# TowerPro_25A_HH30A_V1_1.net
KiCad netlist of a schematic drawn in EAGLE
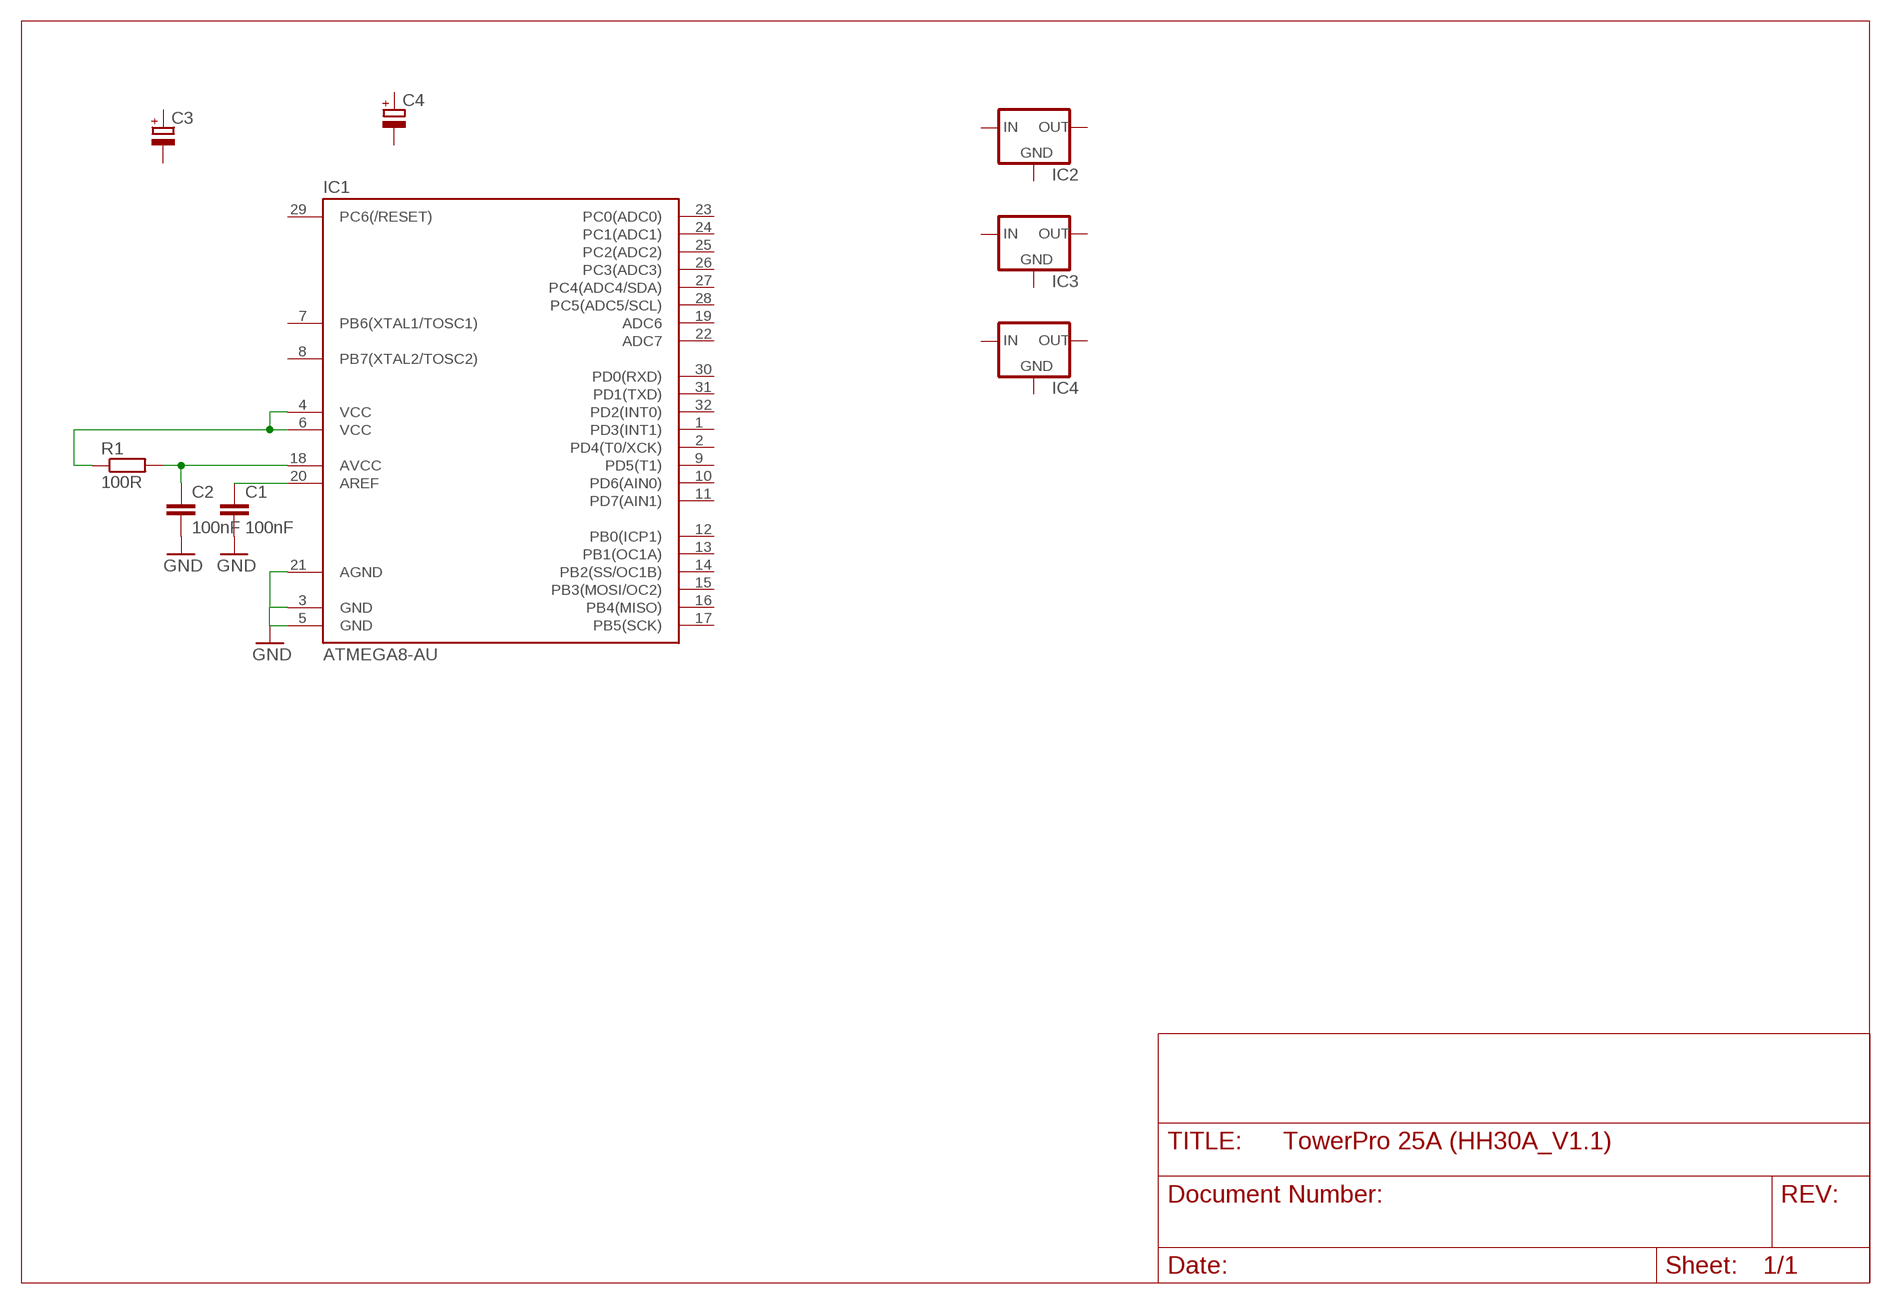
[diagram p0: schematic, sheet 1]

(export (version "E")
  (design (tool "Eeschema 10.0.6"))
  (components
    (comp (ref "C1")
      (value "100nF")
      (footprint "eagle-import:C2.5-3")
      (libsource (lib "eagle-import") (part "C2,5-3"))
    )
    (comp (ref "C2")
      (value "100nF")
      (footprint "eagle-import:C2.5-3")
      (libsource (lib "eagle-import") (part "C2,5-3"))
    )
    (comp (ref "C3")
      (value "CPOL-EUE3.5-10")
      (footprint "eagle-import:E3,5-10")
      (libsource (lib "eagle-import") (part "CPOL-EUE3.5-10"))
    )
    (comp (ref "C4")
      (value "CPOL-EUE3.5-10")
      (footprint "eagle-import:E3,5-10")
      (libsource (lib "eagle-import") (part "CPOL-EUE3.5-10"))
    )
    (comp (ref "IC1")
      (value "ATMEGA8-AU")
      (footprint "eagle-import:TQFP32-08")
      (libsource (lib "eagle-import") (part "ATMEGA8-AU"))
    )
    (comp (ref "IC2")
      (value "78MXXL")
      (footprint "eagle-import:78MXXL")
      (libsource (lib "eagle-import") (part "78MXXL"))
    )
    (comp (ref "IC3")
      (value "78MXXL")
      (footprint "eagle-import:78MXXL")
      (libsource (lib "eagle-import") (part "78MXXL"))
    )
    (comp (ref "IC4")
      (value "78MXXL")
      (footprint "eagle-import:78MXXL")
      (libsource (lib "eagle-import") (part "78MXXL"))
    )
    (comp (ref "R1")
      (value "100R")
      (footprint "eagle-import:M1206")
      (libsource (lib "eagle-import") (part "R-EU_M1206"))
    )
  )
  (nets
    (net (code "1") (name "GND") (class "Default")
      (node (ref "C1") (pin "2") (pinfunction "2_2") (pintype "passive"))
      (node (ref "C2") (pin "2") (pinfunction "2_2") (pintype "passive"))
      (node (ref "IC1") (pin "21") (pinfunction "AGND_21") (pintype "power_in"))
      (node (ref "IC1") (pin "3") (pinfunction "GND_3") (pintype "power_in"))
      (node (ref "IC1") (pin "5") (pinfunction "GND_5") (pintype "power_in"))
    )
    (net (code "2") (name "Net-(IC1-AREF)") (class "Default")
      (node (ref "C1") (pin "1") (pinfunction "1_1") (pintype "passive"))
      (node (ref "IC1") (pin "20") (pinfunction "AREF_20") (pintype "passive"))
    )
    (net (code "3") (name "Net-(IC1-AVCC)") (class "Default")
      (node (ref "C2") (pin "1") (pinfunction "1_1") (pintype "passive"))
      (node (ref "IC1") (pin "18") (pinfunction "AVCC_18") (pintype "passive"))
      (node (ref "R1") (pin "2") (pinfunction "2_2") (pintype "passive"))
    )
    (net (code "4") (name "Net-(IC1-VCC-Pad4)") (class "Default")
      (node (ref "IC1") (pin "4") (pinfunction "VCC_4") (pintype "power_in"))
      (node (ref "IC1") (pin "6") (pinfunction "VCC_6") (pintype "power_in"))
      (node (ref "R1") (pin "1") (pinfunction "1_1") (pintype "passive"))
    )
    (net (code "5") (name "unconnected-(C3-Pad+)") (class "Default")
      (node (ref "C3") (pin "+") (pinfunction "+_+") (pintype "passive"))
    )
    (net (code "6") (name "unconnected-(C3-Pad-)") (class "Default")
      (node (ref "C3") (pin "-") (pinfunction "-_-") (pintype "passive"))
    )
    (net (code "7") (name "unconnected-(C4-Pad+)") (class "Default")
      (node (ref "C4") (pin "+") (pinfunction "+_+") (pintype "passive"))
    )
    (net (code "8") (name "unconnected-(C4-Pad-)") (class "Default")
      (node (ref "C4") (pin "-") (pinfunction "-_-") (pintype "passive"))
    )
    (net (code "9") (name "unconnected-(IC1-ADC6-Pad19)") (class "Default")
      (node (ref "IC1") (pin "19") (pinfunction "ADC6_19") (pintype "passive"))
    )
    (net (code "10") (name "unconnected-(IC1-ADC7-Pad22)") (class "Default")
      (node (ref "IC1") (pin "22") (pinfunction "ADC7_22") (pintype "passive"))
    )
    (net (code "11") (name "unconnected-(IC1-PB0(ICP1)-Pad12)") (class "Default")
      (node (ref "IC1") (pin "12") (pinfunction "PB0(ICP1)_12") (pintype "bidirectional"))
    )
    (net (code "12") (name "unconnected-(IC1-PB1(OC1A)-Pad13)") (class "Default")
      (node (ref "IC1") (pin "13") (pinfunction "PB1(OC1A)_13") (pintype "bidirectional"))
    )
    (net (code "13") (name "unconnected-(IC1-PB2(SS{slash}OC1B)-Pad14)") (class "Default")
      (node (ref "IC1") (pin "14") (pinfunction "PB2(SS/OC1B)_14") (pintype "bidirectional"))
    )
    (net (code "14") (name "unconnected-(IC1-PB3(MOSI{slash}OC2)-Pad15)") (class "Default")
      (node (ref "IC1") (pin "15") (pinfunction "PB3(MOSI/OC2)_15") (pintype "bidirectional"))
    )
    (net (code "15") (name "unconnected-(IC1-PB4(MISO)-Pad16)") (class "Default")
      (node (ref "IC1") (pin "16") (pinfunction "PB4(MISO)_16") (pintype "bidirectional"))
    )
    (net (code "16") (name "unconnected-(IC1-PB5(SCK)-Pad17)") (class "Default")
      (node (ref "IC1") (pin "17") (pinfunction "PB5(SCK)_17") (pintype "bidirectional"))
    )
    (net (code "17") (name "unconnected-(IC1-PB6(XTAL1{slash}TOSC1)-Pad7)") (class "Default")
      (node (ref "IC1") (pin "7") (pinfunction "PB6(XTAL1/TOSC1)_7") (pintype "bidirectional"))
    )
    (net (code "18") (name "unconnected-(IC1-PB7(XTAL2{slash}TOSC2)-Pad8)") (class "Default")
      (node (ref "IC1") (pin "8") (pinfunction "PB7(XTAL2/TOSC2)_8") (pintype "bidirectional"))
    )
    (net (code "19") (name "unconnected-(IC1-PC0(ADC0)-Pad23)") (class "Default")
      (node (ref "IC1") (pin "23") (pinfunction "PC0(ADC0)_23") (pintype "bidirectional"))
    )
    (net (code "20") (name "unconnected-(IC1-PC1(ADC1)-Pad24)") (class "Default")
      (node (ref "IC1") (pin "24") (pinfunction "PC1(ADC1)_24") (pintype "bidirectional"))
    )
    (net (code "21") (name "unconnected-(IC1-PC2(ADC2)-Pad25)") (class "Default")
      (node (ref "IC1") (pin "25") (pinfunction "PC2(ADC2)_25") (pintype "bidirectional"))
    )
    (net (code "22") (name "unconnected-(IC1-PC3(ADC3)-Pad26)") (class "Default")
      (node (ref "IC1") (pin "26") (pinfunction "PC3(ADC3)_26") (pintype "bidirectional"))
    )
    (net (code "23") (name "unconnected-(IC1-PC4(ADC4{slash}SDA)-Pad27)") (class "Default")
      (node (ref "IC1") (pin "27") (pinfunction "PC4(ADC4/SDA)_27") (pintype "bidirectional"))
    )
    (net (code "24") (name "unconnected-(IC1-PC5(ADC5{slash}SCL)-Pad28)") (class "Default")
      (node (ref "IC1") (pin "28") (pinfunction "PC5(ADC5/SCL)_28") (pintype "bidirectional"))
    )
    (net (code "25") (name "unconnected-(IC1-PC6({slash}RESET)-Pad29)") (class "Default")
      (node (ref "IC1") (pin "29") (pinfunction "PC6(/RESET)_29") (pintype "bidirectional"))
    )
    (net (code "26") (name "unconnected-(IC1-PD0(RXD)-Pad30)") (class "Default")
      (node (ref "IC1") (pin "30") (pinfunction "PD0(RXD)_30") (pintype "bidirectional"))
    )
    (net (code "27") (name "unconnected-(IC1-PD1(TXD)-Pad31)") (class "Default")
      (node (ref "IC1") (pin "31") (pinfunction "PD1(TXD)_31") (pintype "bidirectional"))
    )
    (net (code "28") (name "unconnected-(IC1-PD2(INT0)-Pad32)") (class "Default")
      (node (ref "IC1") (pin "32") (pinfunction "PD2(INT0)_32") (pintype "bidirectional"))
    )
    (net (code "29") (name "unconnected-(IC1-PD3(INT1)-Pad1)") (class "Default")
      (node (ref "IC1") (pin "1") (pinfunction "PD3(INT1)_1") (pintype "bidirectional"))
    )
    (net (code "30") (name "unconnected-(IC1-PD4(T0{slash}XCK)-Pad2)") (class "Default")
      (node (ref "IC1") (pin "2") (pinfunction "PD4(T0/XCK)_2") (pintype "bidirectional"))
    )
    (net (code "31") (name "unconnected-(IC1-PD5(T1)-Pad9)") (class "Default")
      (node (ref "IC1") (pin "9") (pinfunction "PD5(T1)_9") (pintype "bidirectional"))
    )
    (net (code "32") (name "unconnected-(IC1-PD6(AIN0)-Pad10)") (class "Default")
      (node (ref "IC1") (pin "10") (pinfunction "PD6(AIN0)_10") (pintype "bidirectional"))
    )
    (net (code "33") (name "unconnected-(IC1-PD7(AIN1)-Pad11)") (class "Default")
      (node (ref "IC1") (pin "11") (pinfunction "PD7(AIN1)_11") (pintype "bidirectional"))
    )
    (net (code "34") (name "unconnected-(IC2-PadGND)") (class "Default")
      (node (ref "IC2") (pin "GND") (pinfunction "GND_GND") (pintype "input"))
    )
    (net (code "35") (name "unconnected-(IC2-PadIN)") (class "Default")
      (node (ref "IC2") (pin "IN") (pinfunction "IN_IN") (pintype "input"))
    )
    (net (code "36") (name "unconnected-(IC2-PadOUT)") (class "Default")
      (node (ref "IC2") (pin "OUT") (pinfunction "OUT_OUT") (pintype "passive"))
    )
    (net (code "37") (name "unconnected-(IC3-PadGND)") (class "Default")
      (node (ref "IC3") (pin "GND") (pinfunction "GND_GND") (pintype "input"))
    )
    (net (code "38") (name "unconnected-(IC3-PadIN)") (class "Default")
      (node (ref "IC3") (pin "IN") (pinfunction "IN_IN") (pintype "input"))
    )
    (net (code "39") (name "unconnected-(IC3-PadOUT)") (class "Default")
      (node (ref "IC3") (pin "OUT") (pinfunction "OUT_OUT") (pintype "passive"))
    )
    (net (code "40") (name "unconnected-(IC4-PadGND)") (class "Default")
      (node (ref "IC4") (pin "GND") (pinfunction "GND_GND") (pintype "input"))
    )
    (net (code "41") (name "unconnected-(IC4-PadIN)") (class "Default")
      (node (ref "IC4") (pin "IN") (pinfunction "IN_IN") (pintype "input"))
    )
    (net (code "42") (name "unconnected-(IC4-PadOUT)") (class "Default")
      (node (ref "IC4") (pin "OUT") (pinfunction "OUT_OUT") (pintype "passive"))
    )
  )
)
